# BC_LCD.net
KiCad netlist of a schematic drawn in EAGLE
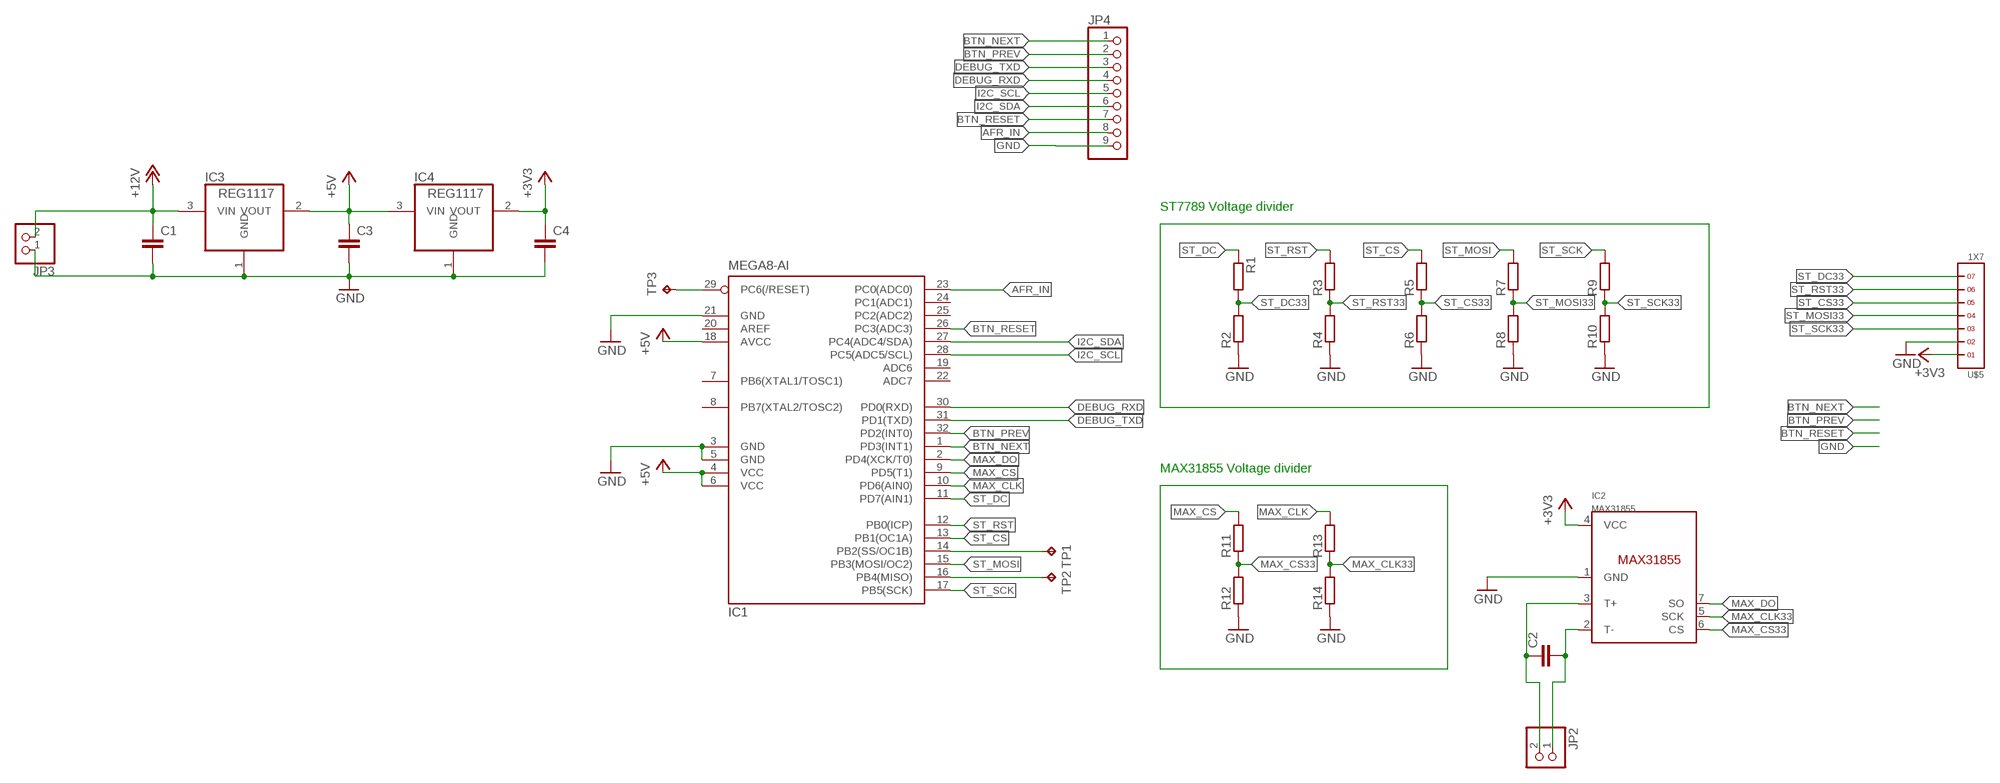
[diagram p0: schematic, sheet 1]

(export (version "E")
  (design (tool "Eeschema 10.0.6"))
  (components
    (comp (ref "C1")
      (value "C-EUC0805K")
      (footprint "eagle-import:C0805K")
      (libsource (lib "eagle-import") (part "C-EUC0805K"))
    )
    (comp (ref "C2")
      (value "C-EUC0805K")
      (footprint "eagle-import:C0805K")
      (libsource (lib "eagle-import") (part "C-EUC0805K"))
    )
    (comp (ref "C3")
      (value "C-EUC0805K")
      (footprint "eagle-import:C0805K")
      (libsource (lib "eagle-import") (part "C-EUC0805K"))
    )
    (comp (ref "C4")
      (value "C-EUC0805K")
      (footprint "eagle-import:C0805K")
      (libsource (lib "eagle-import") (part "C-EUC0805K"))
    )
    (comp (ref "IC1")
      (value "MEGA8-AI")
      (footprint "eagle-import:TQFP32-08")
      (fields (field (name "MPN") "ATMEGA8-16AU"))
      (libsource (lib "eagle-import") (part "MEGA8-AI"))
    )
    (comp (ref "IC2")
      (value "MAX31855")
      (footprint "eagle-import:SOIC8")
      (libsource (lib "eagle-import") (part "MAX31855"))
    )
    (comp (ref "IC3")
      (value "REG1117")
      (footprint "eagle-import:SOT223")
      (libsource (lib "eagle-import") (part "REG1117"))
    )
    (comp (ref "IC4")
      (value "REG1117")
      (footprint "eagle-import:SOT223")
      (libsource (lib "eagle-import") (part "REG1117"))
    )
    (comp (ref "JP2")
      (value "PINHD-1X2")
      (footprint "eagle-import:1X02")
      (libsource (lib "eagle-import") (part "PINHD-1X2"))
    )
    (comp (ref "JP3")
      (value "PINHD-1X2")
      (footprint "eagle-import:1X02")
      (libsource (lib "eagle-import") (part "PINHD-1X2"))
    )
    (comp (ref "JP4")
      (value "PINHD-1X9")
      (footprint "eagle-import:1X09")
      (libsource (lib "eagle-import") (part "PINHD-1X9"))
    )
    (comp (ref "R1")
      (value "R-EU_M0805")
      (footprint "eagle-import:M0805")
      (libsource (lib "eagle-import") (part "R-EU_M0805"))
    )
    (comp (ref "R2")
      (value "R-EU_M0805")
      (footprint "eagle-import:M0805")
      (libsource (lib "eagle-import") (part "R-EU_M0805"))
    )
    (comp (ref "R3")
      (value "R-EU_M0805")
      (footprint "eagle-import:M0805")
      (libsource (lib "eagle-import") (part "R-EU_M0805"))
    )
    (comp (ref "R4")
      (value "R-EU_M0805")
      (footprint "eagle-import:M0805")
      (libsource (lib "eagle-import") (part "R-EU_M0805"))
    )
    (comp (ref "R5")
      (value "R-EU_M0805")
      (footprint "eagle-import:M0805")
      (libsource (lib "eagle-import") (part "R-EU_M0805"))
    )
    (comp (ref "R6")
      (value "R-EU_M0805")
      (footprint "eagle-import:M0805")
      (libsource (lib "eagle-import") (part "R-EU_M0805"))
    )
    (comp (ref "R7")
      (value "R-EU_M0805")
      (footprint "eagle-import:M0805")
      (libsource (lib "eagle-import") (part "R-EU_M0805"))
    )
    (comp (ref "R8")
      (value "R-EU_M0805")
      (footprint "eagle-import:M0805")
      (libsource (lib "eagle-import") (part "R-EU_M0805"))
    )
    (comp (ref "R9")
      (value "R-EU_M0805")
      (footprint "eagle-import:M0805")
      (libsource (lib "eagle-import") (part "R-EU_M0805"))
    )
    (comp (ref "R10")
      (value "R-EU_M0805")
      (footprint "eagle-import:M0805")
      (libsource (lib "eagle-import") (part "R-EU_M0805"))
    )
    (comp (ref "R11")
      (value "R-EU_M0805")
      (footprint "eagle-import:M0805")
      (libsource (lib "eagle-import") (part "R-EU_M0805"))
    )
    (comp (ref "R12")
      (value "R-EU_M0805")
      (footprint "eagle-import:M0805")
      (libsource (lib "eagle-import") (part "R-EU_M0805"))
    )
    (comp (ref "R13")
      (value "R-EU_M0805")
      (footprint "eagle-import:M0805")
      (libsource (lib "eagle-import") (part "R-EU_M0805"))
    )
    (comp (ref "R14")
      (value "R-EU_M0805")
      (footprint "eagle-import:M0805")
      (libsource (lib "eagle-import") (part "R-EU_M0805"))
    )
    (comp (ref "TP1")
      (value "TPTP12R")
      (footprint "eagle-import:TP12R")
      (libsource (lib "eagle-import") (part "TPTP12R"))
    )
    (comp (ref "TP2")
      (value "TPTP12R")
      (footprint "eagle-import:TP12R")
      (libsource (lib "eagle-import") (part "TPTP12R"))
    )
    (comp (ref "TP3")
      (value "TPTP12R")
      (footprint "eagle-import:TP12R")
      (libsource (lib "eagle-import") (part "TPTP12R"))
    )
    (comp (ref "U$5")
      (value "1X7")
      (footprint "eagle-import:1X7")
      (libsource (lib "eagle-import") (part "1X7"))
    )
  )
  (nets
    (net (code "1") (name "+3V3") (class "Default")
      (node (ref "C4") (pin "1") (pinfunction "1_1") (pintype "passive"))
      (node (ref "IC2") (pin "4") (pinfunction "VCC_4") (pintype "power_in"))
      (node (ref "IC4") (pin "2") (pinfunction "VOUT_2") (pintype "output"))
      (node (ref "U$5") (pin "1") (pinfunction "1_1") (pintype "bidirectional"))
    )
    (net (code "2") (name "+5V") (class "Default")
      (node (ref "C3") (pin "1") (pinfunction "1_1") (pintype "passive"))
      (node (ref "IC1") (pin "18") (pinfunction "AVCC_18") (pintype "power_in"))
      (node (ref "IC1") (pin "4") (pinfunction "VCC_4") (pintype "power_in"))
      (node (ref "IC1") (pin "6") (pinfunction "VCC_6") (pintype "power_in"))
      (node (ref "IC3") (pin "2") (pinfunction "VOUT_2") (pintype "output"))
      (node (ref "IC4") (pin "3") (pinfunction "VIN_3") (pintype "input"))
    )
    (net (code "3") (name "+12V") (class "Default")
      (node (ref "C1") (pin "1") (pinfunction "1_1") (pintype "passive"))
      (node (ref "IC3") (pin "3") (pinfunction "VIN_3") (pintype "input"))
      (node (ref "JP3") (pin "2") (pinfunction "2_2") (pintype "passive"))
    )
    (net (code "4") (name "AFR_IN") (class "Default")
      (node (ref "IC1") (pin "23") (pinfunction "PC0(ADC0)_23") (pintype "bidirectional"))
      (node (ref "JP4") (pin "8") (pinfunction "8_8") (pintype "passive"))
    )
    (net (code "5") (name "BTN_NEXT") (class "Default")
      (node (ref "IC1") (pin "1") (pinfunction "PD3(INT1)_1") (pintype "bidirectional"))
      (node (ref "JP4") (pin "1") (pinfunction "1_1") (pintype "passive"))
    )
    (net (code "6") (name "BTN_PREV") (class "Default")
      (node (ref "IC1") (pin "32") (pinfunction "PD2(INT0)_32") (pintype "bidirectional"))
      (node (ref "JP4") (pin "2") (pinfunction "2_2") (pintype "passive"))
    )
    (net (code "7") (name "BTN_RESET") (class "Default")
      (node (ref "IC1") (pin "26") (pinfunction "PC3(ADC3)_26") (pintype "bidirectional"))
      (node (ref "JP4") (pin "7") (pinfunction "7_7") (pintype "passive"))
    )
    (net (code "8") (name "DEBUG_RXD") (class "Default")
      (node (ref "IC1") (pin "30") (pinfunction "PD0(RXD)_30") (pintype "bidirectional"))
      (node (ref "JP4") (pin "4") (pinfunction "4_4") (pintype "passive"))
    )
    (net (code "9") (name "DEBUG_TXD") (class "Default")
      (node (ref "IC1") (pin "31") (pinfunction "PD1(TXD)_31") (pintype "bidirectional"))
      (node (ref "JP4") (pin "3") (pinfunction "3_3") (pintype "passive"))
    )
    (net (code "10") (name "GND") (class "Default")
      (node (ref "C1") (pin "2") (pinfunction "2_2") (pintype "passive"))
      (node (ref "C3") (pin "2") (pinfunction "2_2") (pintype "passive"))
      (node (ref "C4") (pin "2") (pinfunction "2_2") (pintype "passive"))
      (node (ref "IC1") (pin "21") (pinfunction "GND_21") (pintype "power_in"))
      (node (ref "IC1") (pin "3") (pinfunction "GND_3") (pintype "power_in"))
      (node (ref "IC1") (pin "5") (pinfunction "GND_5") (pintype "power_in"))
      (node (ref "IC2") (pin "1") (pinfunction "GND_1") (pintype "power_in"))
      (node (ref "IC3") (pin "1") (pinfunction "GND_1") (pintype "power_in"))
      (node (ref "IC4") (pin "1") (pinfunction "GND_1") (pintype "power_in"))
      (node (ref "JP3") (pin "1") (pinfunction "1_1") (pintype "passive"))
      (node (ref "JP4") (pin "9") (pinfunction "9_9") (pintype "passive"))
      (node (ref "R10") (pin "1") (pinfunction "1_1") (pintype "passive"))
      (node (ref "R12") (pin "1") (pinfunction "1_1") (pintype "passive"))
      (node (ref "R14") (pin "1") (pinfunction "1_1") (pintype "passive"))
      (node (ref "R2") (pin "1") (pinfunction "1_1") (pintype "passive"))
      (node (ref "R4") (pin "1") (pinfunction "1_1") (pintype "passive"))
      (node (ref "R6") (pin "1") (pinfunction "1_1") (pintype "passive"))
      (node (ref "R8") (pin "1") (pinfunction "1_1") (pintype "passive"))
      (node (ref "U$5") (pin "2") (pinfunction "2_2") (pintype "bidirectional"))
    )
    (net (code "11") (name "I2C_SCL") (class "Default")
      (node (ref "IC1") (pin "28") (pinfunction "PC5(ADC5/SCL)_28") (pintype "bidirectional"))
      (node (ref "JP4") (pin "5") (pinfunction "5_5") (pintype "passive"))
    )
    (net (code "12") (name "I2C_SDA") (class "Default")
      (node (ref "IC1") (pin "27") (pinfunction "PC4(ADC4/SDA)_27") (pintype "bidirectional"))
      (node (ref "JP4") (pin "6") (pinfunction "6_6") (pintype "passive"))
    )
    (net (code "13") (name "MAX_CLK") (class "Default")
      (node (ref "IC1") (pin "10") (pinfunction "PD6(AIN0)_10") (pintype "bidirectional"))
      (node (ref "R13") (pin "2") (pinfunction "2_2") (pintype "passive"))
    )
    (net (code "14") (name "MAX_CLK33") (class "Default")
      (node (ref "IC2") (pin "5") (pinfunction "SCK_5") (pintype "input"))
      (node (ref "R13") (pin "1") (pinfunction "1_1") (pintype "passive"))
      (node (ref "R14") (pin "2") (pinfunction "2_2") (pintype "passive"))
    )
    (net (code "15") (name "MAX_CS") (class "Default")
      (node (ref "IC1") (pin "9") (pinfunction "PD5(T1)_9") (pintype "bidirectional"))
      (node (ref "R11") (pin "2") (pinfunction "2_2") (pintype "passive"))
    )
    (net (code "16") (name "MAX_CS33") (class "Default")
      (node (ref "IC2") (pin "6") (pinfunction "CS_6") (pintype "input"))
      (node (ref "R11") (pin "1") (pinfunction "1_1") (pintype "passive"))
      (node (ref "R12") (pin "2") (pinfunction "2_2") (pintype "passive"))
    )
    (net (code "17") (name "MAX_DO") (class "Default")
      (node (ref "IC1") (pin "2") (pinfunction "PD4(XCK/T0)_2") (pintype "bidirectional"))
      (node (ref "IC2") (pin "7") (pinfunction "SO_7") (pintype "output"))
    )
    (net (code "18") (name "Net-(IC1-PB2(SS{slash}OC1B))") (class "Default")
      (node (ref "IC1") (pin "14") (pinfunction "PB2(SS/OC1B)_14") (pintype "bidirectional"))
      (node (ref "TP1") (pin "TP") (pinfunction "TP_TP") (pintype "input"))
    )
    (net (code "19") (name "Net-(IC1-PB4(MISO))") (class "Default")
      (node (ref "IC1") (pin "16") (pinfunction "PB4(MISO)_16") (pintype "bidirectional"))
      (node (ref "TP2") (pin "TP") (pinfunction "TP_TP") (pintype "input"))
    )
    (net (code "20") (name "Net-(IC1-PC6({slash}RESET))") (class "Default")
      (node (ref "IC1") (pin "29") (pinfunction "PC6(/RESET)_29") (pintype "bidirectional"))
      (node (ref "TP3") (pin "TP") (pinfunction "TP_TP") (pintype "input"))
    )
    (net (code "21") (name "Net-(IC2-T+)") (class "Default")
      (node (ref "C2") (pin "1") (pinfunction "1_1") (pintype "passive"))
      (node (ref "IC2") (pin "3") (pinfunction "T+_3") (pintype "input"))
      (node (ref "JP2") (pin "2") (pinfunction "2_2") (pintype "passive"))
    )
    (net (code "22") (name "Net-(IC2-T-)") (class "Default")
      (node (ref "C2") (pin "2") (pinfunction "2_2") (pintype "passive"))
      (node (ref "IC2") (pin "2") (pinfunction "T-_2") (pintype "input"))
      (node (ref "JP2") (pin "1") (pinfunction "1_1") (pintype "passive"))
    )
    (net (code "23") (name "ST_CS") (class "Default")
      (node (ref "IC1") (pin "13") (pinfunction "PB1(OC1A)_13") (pintype "bidirectional"))
      (node (ref "R5") (pin "2") (pinfunction "2_2") (pintype "passive"))
    )
    (net (code "24") (name "ST_CS33") (class "Default")
      (node (ref "R5") (pin "1") (pinfunction "1_1") (pintype "passive"))
      (node (ref "R6") (pin "2") (pinfunction "2_2") (pintype "passive"))
      (node (ref "U$5") (pin "5") (pinfunction "5_5") (pintype "bidirectional"))
    )
    (net (code "25") (name "ST_DC") (class "Default")
      (node (ref "IC1") (pin "11") (pinfunction "PD7(AIN1)_11") (pintype "bidirectional"))
      (node (ref "R1") (pin "1") (pinfunction "1_1") (pintype "passive"))
    )
    (net (code "26") (name "ST_DC33") (class "Default")
      (node (ref "R1") (pin "2") (pinfunction "2_2") (pintype "passive"))
      (node (ref "R2") (pin "2") (pinfunction "2_2") (pintype "passive"))
      (node (ref "U$5") (pin "7") (pinfunction "7_7") (pintype "bidirectional"))
    )
    (net (code "27") (name "ST_MOSI") (class "Default")
      (node (ref "IC1") (pin "15") (pinfunction "PB3(MOSI/OC2)_15") (pintype "bidirectional"))
      (node (ref "R7") (pin "2") (pinfunction "2_2") (pintype "passive"))
    )
    (net (code "28") (name "ST_MOSI33") (class "Default")
      (node (ref "R7") (pin "1") (pinfunction "1_1") (pintype "passive"))
      (node (ref "R8") (pin "2") (pinfunction "2_2") (pintype "passive"))
      (node (ref "U$5") (pin "4") (pinfunction "4_4") (pintype "bidirectional"))
    )
    (net (code "29") (name "ST_RST") (class "Default")
      (node (ref "IC1") (pin "12") (pinfunction "PB0(ICP)_12") (pintype "bidirectional"))
      (node (ref "R3") (pin "2") (pinfunction "2_2") (pintype "passive"))
    )
    (net (code "30") (name "ST_RST33") (class "Default")
      (node (ref "R3") (pin "1") (pinfunction "1_1") (pintype "passive"))
      (node (ref "R4") (pin "2") (pinfunction "2_2") (pintype "passive"))
      (node (ref "U$5") (pin "6") (pinfunction "6_6") (pintype "bidirectional"))
    )
    (net (code "31") (name "ST_SCK") (class "Default")
      (node (ref "IC1") (pin "17") (pinfunction "PB5(SCK)_17") (pintype "bidirectional"))
      (node (ref "R9") (pin "2") (pinfunction "2_2") (pintype "passive"))
    )
    (net (code "32") (name "ST_SCK33") (class "Default")
      (node (ref "R10") (pin "2") (pinfunction "2_2") (pintype "passive"))
      (node (ref "R9") (pin "1") (pinfunction "1_1") (pintype "passive"))
      (node (ref "U$5") (pin "3") (pinfunction "3_3") (pintype "bidirectional"))
    )
    (net (code "33") (name "unconnected-(IC1-ADC6-Pad19)") (class "Default")
      (node (ref "IC1") (pin "19") (pinfunction "ADC6_19") (pintype "bidirectional"))
    )
    (net (code "34") (name "unconnected-(IC1-ADC7-Pad22)") (class "Default")
      (node (ref "IC1") (pin "22") (pinfunction "ADC7_22") (pintype "bidirectional"))
    )
    (net (code "35") (name "unconnected-(IC1-AREF-Pad20)") (class "Default")
      (node (ref "IC1") (pin "20") (pinfunction "AREF_20") (pintype "passive"))
    )
    (net (code "36") (name "unconnected-(IC1-PB6(XTAL1{slash}TOSC1)-Pad7)") (class "Default")
      (node (ref "IC1") (pin "7") (pinfunction "PB6(XTAL1/TOSC1)_7") (pintype "bidirectional"))
    )
    (net (code "37") (name "unconnected-(IC1-PB7(XTAL2{slash}TOSC2)-Pad8)") (class "Default")
      (node (ref "IC1") (pin "8") (pinfunction "PB7(XTAL2/TOSC2)_8") (pintype "bidirectional"))
    )
    (net (code "38") (name "unconnected-(IC1-PC1(ADC1)-Pad24)") (class "Default")
      (node (ref "IC1") (pin "24") (pinfunction "PC1(ADC1)_24") (pintype "bidirectional"))
    )
    (net (code "39") (name "unconnected-(IC1-PC2(ADC2)-Pad25)") (class "Default")
      (node (ref "IC1") (pin "25") (pinfunction "PC2(ADC2)_25") (pintype "bidirectional"))
    )
  )
)
